# simon-7segment.net
KiCad netlist of a schematic drawn in EAGLE
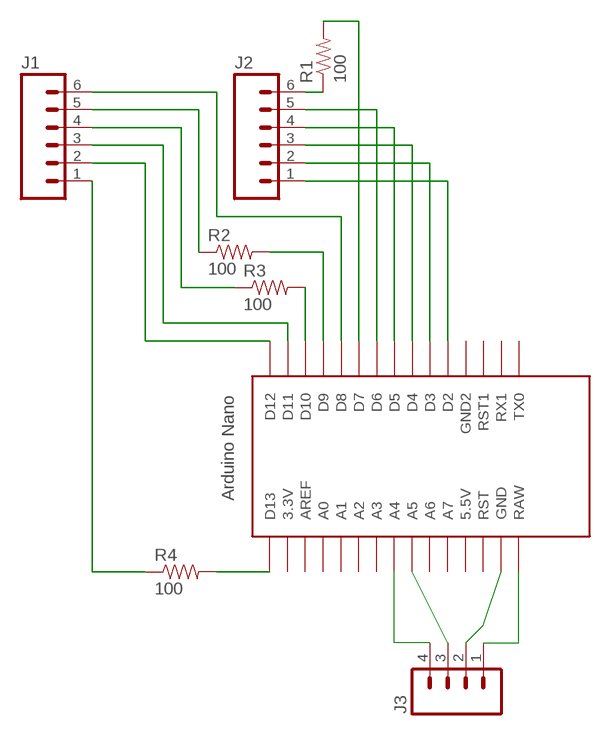
[diagram p0: schematic, sheet 1]

(export (version "E")
  (design (tool "Eeschema 10.0.6"))
  (components
    (comp (ref "J1")
      (value "M06SILK_FEMALE_PTH")
      (footprint "eagle-import:1X06")
      (libsource (lib "eagle-import") (part "M06SILK_FEMALE_PTH"))
    )
    (comp (ref "J2")
      (value "M06SILK_FEMALE_PTH")
      (footprint "eagle-import:1X06")
      (libsource (lib "eagle-import") (part "M06SILK_FEMALE_PTH"))
    )
    (comp (ref "J3")
      (value "M04LOCK_LONGPADS")
      (footprint "eagle-import:1X04_LOCK_LONGPADS")
      (libsource (lib "eagle-import") (part "M04LOCK_LONGPADS"))
    )
    (comp (ref "R1")
      (value "100")
      (footprint "eagle-import:AXIAL-0.4")
      (libsource (lib "eagle-import") (part "RESISTORPTH-1/4W"))
    )
    (comp (ref "R2")
      (value "100")
      (footprint "eagle-import:AXIAL-0.4")
      (libsource (lib "eagle-import") (part "RESISTORPTH-1/4W"))
    )
    (comp (ref "R3")
      (value "100")
      (footprint "eagle-import:AXIAL-0.4")
      (libsource (lib "eagle-import") (part "RESISTORPTH-1/4W"))
    )
    (comp (ref "R4")
      (value "100")
      (footprint "eagle-import:AXIAL-0.4")
      (libsource (lib "eagle-import") (part "RESISTORPTH-1/4W"))
    )
    (comp (ref "U$1")
      (value "NANO")
      (footprint "eagle-import:NANO")
      (libsource (lib "eagle-import") (part "NANO"))
    )
  )
  (nets
    (net (code "1") (name "Net-(J1-Pad2)") (class "Default")
      (node (ref "J1") (pin "2") (pinfunction "2_2") (pintype "passive"))
      (node (ref "U$1") (pin "D12") (pinfunction "D12_D12") (pintype "bidirectional"))
    )
    (net (code "2") (name "Net-(J1-Pad3)") (class "Default")
      (node (ref "J1") (pin "3") (pinfunction "3_3") (pintype "passive"))
      (node (ref "U$1") (pin "D11") (pinfunction "D11_D11") (pintype "bidirectional"))
    )
    (net (code "3") (name "Net-(J1-Pad6)") (class "Default")
      (node (ref "J1") (pin "6") (pinfunction "6_6") (pintype "passive"))
      (node (ref "U$1") (pin "D8") (pinfunction "D8_D8") (pintype "bidirectional"))
    )
    (net (code "4") (name "Net-(J2-Pad1)") (class "Default")
      (node (ref "J2") (pin "1") (pinfunction "1_1") (pintype "passive"))
      (node (ref "U$1") (pin "D2") (pinfunction "D2_D2") (pintype "bidirectional"))
    )
    (net (code "5") (name "Net-(J2-Pad2)") (class "Default")
      (node (ref "J2") (pin "2") (pinfunction "2_2") (pintype "passive"))
      (node (ref "U$1") (pin "D3") (pinfunction "D3_D3") (pintype "bidirectional"))
    )
    (net (code "6") (name "Net-(J2-Pad3)") (class "Default")
      (node (ref "J2") (pin "3") (pinfunction "3_3") (pintype "passive"))
      (node (ref "U$1") (pin "D4") (pinfunction "D4_D4") (pintype "bidirectional"))
    )
    (net (code "7") (name "Net-(J2-Pad4)") (class "Default")
      (node (ref "J2") (pin "4") (pinfunction "4_4") (pintype "passive"))
      (node (ref "U$1") (pin "D5") (pinfunction "D5_D5") (pintype "bidirectional"))
    )
    (net (code "8") (name "Net-(J2-Pad5)") (class "Default")
      (node (ref "J2") (pin "5") (pinfunction "5_5") (pintype "passive"))
      (node (ref "U$1") (pin "D6") (pinfunction "D6_D6") (pintype "bidirectional"))
    )
    (net (code "9") (name "Net-(J3-Pad1)") (class "Default")
      (node (ref "J3") (pin "1") (pinfunction "1_1") (pintype "passive"))
      (node (ref "U$1") (pin "RAW") (pinfunction "RAW_RAW") (pintype "bidirectional"))
    )
    (net (code "10") (name "Net-(J3-Pad2)") (class "Default")
      (node (ref "J3") (pin "2") (pinfunction "2_2") (pintype "passive"))
      (node (ref "U$1") (pin "GND") (pinfunction "GND_GND") (pintype "bidirectional"))
    )
    (net (code "11") (name "Net-(J3-Pad3)") (class "Default")
      (node (ref "J3") (pin "3") (pinfunction "3_3") (pintype "passive"))
      (node (ref "U$1") (pin "A5") (pinfunction "A5_A5") (pintype "bidirectional"))
    )
    (net (code "12") (name "Net-(J3-Pad4)") (class "Default")
      (node (ref "J3") (pin "4") (pinfunction "4_4") (pintype "passive"))
      (node (ref "U$1") (pin "A4") (pinfunction "A4_A4") (pintype "bidirectional"))
    )
    (net (code "13") (name "Net-(R1-1)") (class "Default")
      (node (ref "J2") (pin "6") (pinfunction "6_6") (pintype "passive"))
      (node (ref "R1") (pin "P$1") (pinfunction "1_P$1") (pintype "passive"))
    )
    (net (code "14") (name "Net-(R1-2)") (class "Default")
      (node (ref "R1") (pin "P$2") (pinfunction "2_P$2") (pintype "passive"))
      (node (ref "U$1") (pin "D7") (pinfunction "D7_D7") (pintype "bidirectional"))
    )
    (net (code "15") (name "Net-(R2-1)") (class "Default")
      (node (ref "J1") (pin "5") (pinfunction "5_5") (pintype "passive"))
      (node (ref "R2") (pin "P$1") (pinfunction "1_P$1") (pintype "passive"))
    )
    (net (code "16") (name "Net-(R2-2)") (class "Default")
      (node (ref "R2") (pin "P$2") (pinfunction "2_P$2") (pintype "passive"))
      (node (ref "U$1") (pin "D9") (pinfunction "D9_D9") (pintype "bidirectional"))
    )
    (net (code "17") (name "Net-(R3-1)") (class "Default")
      (node (ref "J1") (pin "4") (pinfunction "4_4") (pintype "passive"))
      (node (ref "R3") (pin "P$1") (pinfunction "1_P$1") (pintype "passive"))
    )
    (net (code "18") (name "Net-(R3-2)") (class "Default")
      (node (ref "R3") (pin "P$2") (pinfunction "2_P$2") (pintype "passive"))
      (node (ref "U$1") (pin "D10") (pinfunction "D10_D10") (pintype "bidirectional"))
    )
    (net (code "19") (name "Net-(R4-1)") (class "Default")
      (node (ref "J1") (pin "1") (pinfunction "1_1") (pintype "passive"))
      (node (ref "R4") (pin "P$1") (pinfunction "1_P$1") (pintype "passive"))
    )
    (net (code "20") (name "Net-(R4-2)") (class "Default")
      (node (ref "R4") (pin "P$2") (pinfunction "2_P$2") (pintype "passive"))
      (node (ref "U$1") (pin "D13") (pinfunction "D13_D13") (pintype "bidirectional"))
    )
    (net (code "21") (name "unconnected-(U$1-5.5V-Pad5V)") (class "Default")
      (node (ref "U$1") (pin "5V") (pinfunction "5.5V_5V") (pintype "bidirectional"))
    )
    (net (code "22") (name "unconnected-(U$1-GND2-PadGND1)") (class "Default")
      (node (ref "U$1") (pin "GND1") (pinfunction "GND2_GND1") (pintype "bidirectional"))
    )
    (net (code "23") (name "unconnected-(U$1-Pad3.3V)") (class "Default")
      (node (ref "U$1") (pin "3.3V") (pinfunction "3.3V_3.3V") (pintype "bidirectional"))
    )
    (net (code "24") (name "unconnected-(U$1-PadA0)") (class "Default")
      (node (ref "U$1") (pin "A0") (pinfunction "A0_A0") (pintype "bidirectional"))
    )
    (net (code "25") (name "unconnected-(U$1-PadA1)") (class "Default")
      (node (ref "U$1") (pin "A1") (pinfunction "A1_A1") (pintype "bidirectional"))
    )
    (net (code "26") (name "unconnected-(U$1-PadA2)") (class "Default")
      (node (ref "U$1") (pin "A2") (pinfunction "A2_A2") (pintype "bidirectional"))
    )
    (net (code "27") (name "unconnected-(U$1-PadA3)") (class "Default")
      (node (ref "U$1") (pin "A3") (pinfunction "A3_A3") (pintype "bidirectional"))
    )
    (net (code "28") (name "unconnected-(U$1-PadA6)") (class "Default")
      (node (ref "U$1") (pin "A6") (pinfunction "A6_A6") (pintype "bidirectional"))
    )
    (net (code "29") (name "unconnected-(U$1-PadA7)") (class "Default")
      (node (ref "U$1") (pin "A7") (pinfunction "A7_A7") (pintype "bidirectional"))
    )
    (net (code "30") (name "unconnected-(U$1-PadAREF)") (class "Default")
      (node (ref "U$1") (pin "AREF") (pinfunction "AREF_AREF") (pintype "bidirectional"))
    )
    (net (code "31") (name "unconnected-(U$1-PadICSP1)") (class "Default")
      (node (ref "U$1") (pin "ICSP1") (pinfunction "ICSP1_ICSP1") (pintype "bidirectional"))
    )
    (net (code "32") (name "unconnected-(U$1-PadICSP2)") (class "Default")
      (node (ref "U$1") (pin "ICSP2") (pinfunction "ICSP2_ICSP2") (pintype "bidirectional"))
    )
    (net (code "33") (name "unconnected-(U$1-PadICSP3)") (class "Default")
      (node (ref "U$1") (pin "ICSP3") (pinfunction "ICSP3_ICSP3") (pintype "bidirectional"))
    )
    (net (code "34") (name "unconnected-(U$1-PadICSP4)") (class "Default")
      (node (ref "U$1") (pin "ICSP4") (pinfunction "ICSP4_ICSP4") (pintype "bidirectional"))
    )
    (net (code "35") (name "unconnected-(U$1-PadICSP5)") (class "Default")
      (node (ref "U$1") (pin "ICSP5") (pinfunction "ICSP5_ICSP5") (pintype "bidirectional"))
    )
    (net (code "36") (name "unconnected-(U$1-PadICSP6)") (class "Default")
      (node (ref "U$1") (pin "ICSP6") (pinfunction "ICSP6_ICSP6") (pintype "bidirectional"))
    )
    (net (code "37") (name "unconnected-(U$1-PadRST)") (class "Default")
      (node (ref "U$1") (pin "RST") (pinfunction "RST_RST") (pintype "bidirectional"))
    )
    (net (code "38") (name "unconnected-(U$1-PadRST1)") (class "Default")
      (node (ref "U$1") (pin "RST1") (pinfunction "RST1_RST1") (pintype "bidirectional"))
    )
    (net (code "39") (name "unconnected-(U$1-PadRX1)") (class "Default")
      (node (ref "U$1") (pin "RX1") (pinfunction "RX1_RX1") (pintype "bidirectional"))
    )
    (net (code "40") (name "unconnected-(U$1-PadTX0)") (class "Default")
      (node (ref "U$1") (pin "TX0") (pinfunction "TX0_TX0") (pintype "bidirectional"))
    )
  )
)
